# sb-sonata-debug.net
KiCad netlist of a schematic drawn in Altium Designer
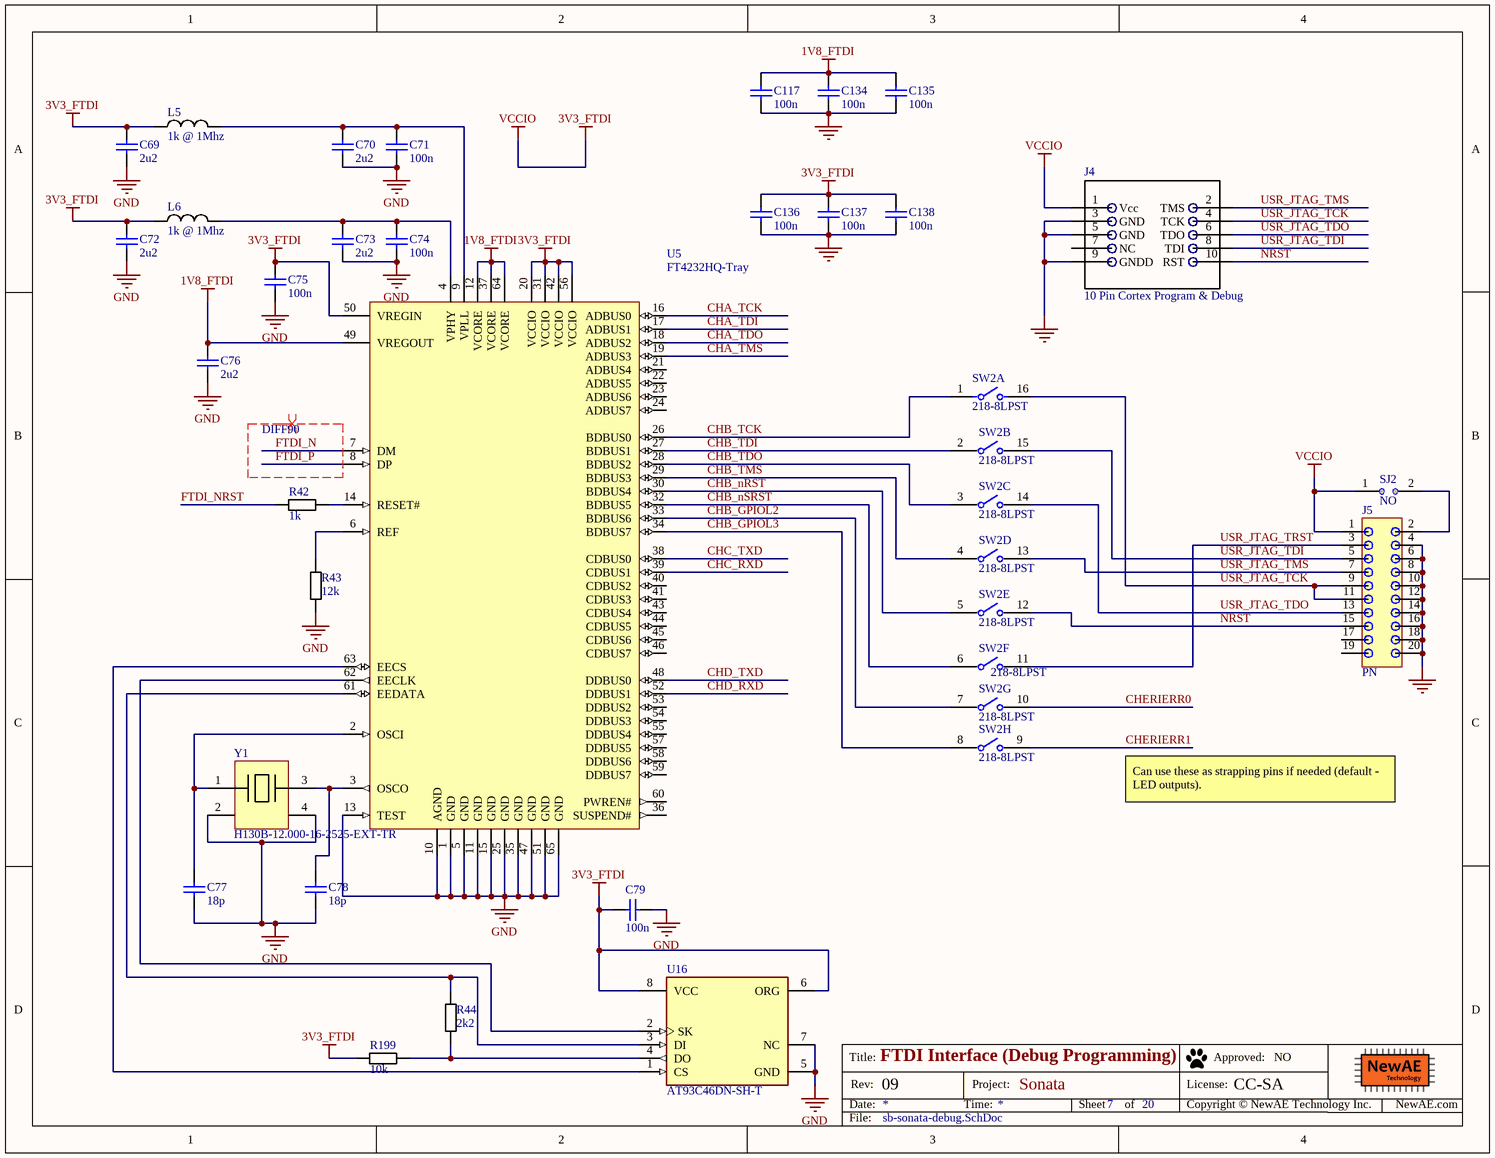
[diagram p0: sb-sonata-debug.SchDoc]

(export (version "E")
  (design (tool "Eeschema 10.0.6"))
  (components
    (comp (ref "C69")
      (value "2u2")
      (footprint "CAPC0603_M")
      (description "2u2, 0603")
      (fields (field (name "PART NUMBER") "CCHIP-2u2-0603"))
      (libsource (lib "NewAE_AltiumLib") (part "CAP"))
    )
    (comp (ref "C70")
      (value "2u2")
      (footprint "CAPC0603_M")
      (description "2u2, 0603")
      (fields (field (name "PART NUMBER") "CCHIP-2u2-0603"))
      (libsource (lib "NewAE_AltiumLib") (part "CAP"))
    )
    (comp (ref "C71")
      (value "100n")
      (footprint "CAPC0402_M")
      (description "100n, 0402")
      (fields (field (name "PART NUMBER") "CCHIP-100n-0402"))
      (libsource (lib "NewAE_AltiumLib") (part "CAP"))
    )
    (comp (ref "C72")
      (value "2u2")
      (footprint "CAPC0603_M")
      (description "2u2, 0603")
      (fields (field (name "PART NUMBER") "CCHIP-2u2-0603"))
      (libsource (lib "NewAE_AltiumLib") (part "CAP"))
    )
    (comp (ref "C73")
      (value "2u2")
      (footprint "CAPC0603_M")
      (description "2u2, 0603")
      (fields (field (name "PART NUMBER") "CCHIP-2u2-0603"))
      (libsource (lib "NewAE_AltiumLib") (part "CAP"))
    )
    (comp (ref "C74")
      (value "100n")
      (footprint "CAPC0402_M")
      (description "100n, 0402")
      (fields (field (name "PART NUMBER") "CCHIP-100n-0402"))
      (libsource (lib "NewAE_AltiumLib") (part "CAP"))
    )
    (comp (ref "C75")
      (value "100n")
      (footprint "CAPC0402_M")
      (description "100n, 0402")
      (fields (field (name "PART NUMBER") "CCHIP-100n-0402"))
      (libsource (lib "NewAE_AltiumLib") (part "CAP"))
    )
    (comp (ref "C76")
      (value "2u2")
      (footprint "CAPC0603_M")
      (description "2u2, 0603")
      (fields (field (name "PART NUMBER") "CCHIP-2u2-0603"))
      (libsource (lib "NewAE_AltiumLib") (part "CAP"))
    )
    (comp (ref "C77")
      (value "18p")
      (footprint "CAPC0402_M")
      (description "18p, 0402")
      (fields (field (name "PART NUMBER") "CCHIP-18p-0402"))
      (libsource (lib "NewAE_AltiumLib") (part "CAP"))
    )
    (comp (ref "C78")
      (value "18p")
      (footprint "CAPC0402_M")
      (description "18p, 0402")
      (fields (field (name "PART NUMBER") "CCHIP-18p-0402"))
      (libsource (lib "NewAE_AltiumLib") (part "CAP"))
    )
    (comp (ref "C79")
      (value "100n")
      (footprint "CAPC0402_M")
      (description "100n, 0402")
      (fields (field (name "PART NUMBER") "CCHIP-100n-0402"))
      (libsource (lib "NewAE_AltiumLib") (part "CAP"))
    )
    (comp (ref "C117")
      (value "100n")
      (footprint "CAPC0402_M")
      (description "100n, 0402")
      (fields (field (name "PART NUMBER") "CCHIP-100n-0402"))
      (libsource (lib "NewAE_AltiumLib") (part "CAP"))
    )
    (comp (ref "C134")
      (value "100n")
      (footprint "CAPC0402_M")
      (description "100n, 0402")
      (fields (field (name "PART NUMBER") "CCHIP-100n-0402"))
      (libsource (lib "NewAE_AltiumLib") (part "CAP"))
    )
    (comp (ref "C135")
      (value "100n")
      (footprint "CAPC0402_M")
      (description "100n, 0402")
      (fields (field (name "PART NUMBER") "CCHIP-100n-0402"))
      (libsource (lib "NewAE_AltiumLib") (part "CAP"))
    )
    (comp (ref "C136")
      (value "100n")
      (footprint "CAPC0402_M")
      (description "100n, 0402")
      (fields (field (name "PART NUMBER") "CCHIP-100n-0402"))
      (libsource (lib "NewAE_AltiumLib") (part "CAP"))
    )
    (comp (ref "C137")
      (value "100n")
      (footprint "CAPC0402_M")
      (description "100n, 0402")
      (fields (field (name "PART NUMBER") "CCHIP-100n-0402"))
      (libsource (lib "NewAE_AltiumLib") (part "CAP"))
    )
    (comp (ref "C138")
      (value "100n")
      (footprint "CAPC0402_M")
      (description "100n, 0402")
      (fields (field (name "PART NUMBER") "CCHIP-100n-0402"))
      (libsource (lib "NewAE_AltiumLib") (part "CAP"))
    )
    (comp (ref "J4")
      (value "10 Pin Cortex Program & Debug")
      (footprint "0.5mm_SMD_Header_5x2")
      (description "10 Pin Cortex Program & Debug 0.5mm pitch")
      (fields (field (name "PART NUMBER") "Cortex_Debug_Header_10Pin"))
      (libsource (lib "NewAE_AltiumLib") (part "Cortex_Debug_Header_10Pin"))
    )
    (comp (ref "J5")
      (value "PN")
      (footprint "CONN_10x2_SHROUDED_2.54mm")
      (description "Header, 2-Row, 20-pin, 0.1\"")
      (fields (field (name "PART NUMBER") "CONN20_2ROW"))
      (libsource (lib "NewAE_AltiumLib") (part "CON20_2ROW"))
    )
    (comp (ref "L5")
      (value "1k @ 1Mhz")
      (footprint "IND_0603")
      (description "Ferrite Beads HI CUR CHIP BD 0603 1000OHMS 25%")
      (fields (field (name "PART NUMBER") "FBCHIP-1k-0603"))
      (libsource (lib "NewAE_AltiumLib") (part "IND"))
    )
    (comp (ref "L6")
      (value "1k @ 1Mhz")
      (footprint "IND_0603")
      (description "Ferrite Beads HI CUR CHIP BD 0603 1000OHMS 25%")
      (fields (field (name "PART NUMBER") "FBCHIP-1k-0603"))
      (libsource (lib "NewAE_AltiumLib") (part "IND"))
    )
    (comp (ref "R42")
      (value "1k")
      (footprint "RESC1005X40N")
      (description "1k res, 0402, 1%, 1/16W")
      (fields (field (name "PART NUMBER") "RCHIP-1K-0402") (field (name "TOLERANCE") "1%"))
      (libsource (lib "NewAE_AltiumLib") (part "RES-EU"))
    )
    (comp (ref "R43")
      (value "12k")
      (footprint "RESC1608X55N")
      (description "12k res, 0603, 1%, 1/10W")
      (fields (field (name "PART NUMBER") "RCHIP-12K-0603") (field (name "TOLERANCE") "1%"))
      (libsource (lib "") (part "RES-EU_2"))
    )
    (comp (ref "R44")
      (value "2k2")
      (footprint "RESC1005X40N")
      (description "2k2 res, 0402, 1%, 1/16W")
      (fields (field (name "PART NUMBER") "RCHIP-2K2-0402") (field (name "TOLERANCE") "1%"))
      (libsource (lib "") (part "RES-EU_2"))
    )
    (comp (ref "R199")
      (value "10k")
      (footprint "RESC1005X40N")
      (description "10k res, 0402, 1%, 1/16W")
      (fields (field (name "PART NUMBER") "RCHIP-10K-0402") (field (name "TOLERANCE") "1%"))
      (libsource (lib "") (part "RES-EU_1"))
    )
    (comp (ref "SJ2")
      (value "NO")
      (footprint "SJ_2S_NO")
      (description "Solder Jumper, NO")
      (fields (field (name "PART NUMBER") "SJ_2S_NO"))
      (libsource (lib "NewAE_AltiumLib") (part "SJ_2S_NO"))
    )
    (comp (ref "SW2")
      (value "218-8LPST")
      (footprint "FP-218-8LPST-MFG")
      (description "SWITCH SLIDE DIP SPST 25MA 24V")
      (libsource (lib "Altium Content Vault") (part "c442af63ff53b934e43635f80d8690e"))
    )
    (comp (ref "U5")
      (value "FT4232HQ-Tray")
      (footprint "QFN64_2_N")
      (description "Quad High Speed USB To Multipurpose UART/MPSSE IC, 64-pin QFN, Tray")
      (fields (field (name "MANUFACTURER") "FTDI"))
      (libsource (lib "Altium Content Vault") (part "COM-UART-FT4232H-QFN64"))
    )
    (comp (ref "U16")
      (value "AT93C46DN-SH-T")
      (footprint "FP-C04-057-SN-MFG")
      (description "IC EEPROM 1K SPI 2MHZ 8SOIC")
      (fields
        (field (name "MANUFACTURER") "Microchip")
        (field (name "OCTOPART") "https://octopart.com/at93c46dn-sh-t-microchip-77759177")
      )
      (libsource (lib "Altium Content Vault") (part "8bb9afc094b350e480db350c7247e52"))
    )
    (comp (ref "Y1")
      (value "H130B-12.000-16-2525-EXT-TR")
      (footprint "5x3.2MM XTAL")
      (description "12MHz ±25ppm Crystal 16pF 35 Ohms 4-SMD, No Lead")
      (fields (field (name "MANUFACTURER PART NUMBER") "H130B-12.000-16-2525-EXT-TR"))
      (libsource (lib "NewAE_AltiumLib") (part "H130B-12.000-16-2525-EXT-TR"))
    )
  )
  (nets
    (net (code "1") (name "/CHA_TCK") (class "Default")
      (node (ref "U5") (pin "16") (pinfunction "ADBUS0_16") (pintype "bidirectional"))
    )
    (net (code "2") (name "/CHA_TDI") (class "Default")
      (node (ref "U5") (pin "17") (pinfunction "ADBUS1_17") (pintype "bidirectional"))
    )
    (net (code "3") (name "/CHA_TDO") (class "Default")
      (node (ref "U5") (pin "18") (pinfunction "ADBUS2_18") (pintype "bidirectional"))
    )
    (net (code "4") (name "/CHA_TMS") (class "Default")
      (node (ref "U5") (pin "19") (pinfunction "ADBUS3_19") (pintype "bidirectional"))
    )
    (net (code "5") (name "/CHB_GPIOL2") (class "Default")
      (node (ref "SW2") (pin "7") (pinfunction "7_7") (pintype "passive"))
      (node (ref "U5") (pin "33") (pinfunction "BDBUS6_33") (pintype "bidirectional"))
    )
    (net (code "6") (name "/CHB_GPIOL3") (class "Default")
      (node (ref "SW2") (pin "8") (pinfunction "8_8") (pintype "passive"))
      (node (ref "U5") (pin "34") (pinfunction "BDBUS7_34") (pintype "bidirectional"))
    )
    (net (code "7") (name "/CHB_TCK") (class "Default")
      (node (ref "SW2") (pin "1") (pinfunction "1_1") (pintype "passive"))
      (node (ref "U5") (pin "26") (pinfunction "BDBUS0_26") (pintype "bidirectional"))
    )
    (net (code "8") (name "/CHB_TDI") (class "Default")
      (node (ref "SW2") (pin "2") (pinfunction "2_2") (pintype "passive"))
      (node (ref "U5") (pin "27") (pinfunction "BDBUS1_27") (pintype "bidirectional"))
    )
    (net (code "9") (name "/CHB_TDO") (class "Default")
      (node (ref "SW2") (pin "3") (pinfunction "3_3") (pintype "passive"))
      (node (ref "U5") (pin "28") (pinfunction "BDBUS2_28") (pintype "bidirectional"))
    )
    (net (code "10") (name "/CHB_TMS") (class "Default")
      (node (ref "SW2") (pin "4") (pinfunction "4_4") (pintype "passive"))
      (node (ref "U5") (pin "29") (pinfunction "BDBUS3_29") (pintype "bidirectional"))
    )
    (net (code "11") (name "/CHB_nRST") (class "Default")
      (node (ref "SW2") (pin "5") (pinfunction "5_5") (pintype "passive"))
      (node (ref "U5") (pin "30") (pinfunction "BDBUS4_30") (pintype "bidirectional"))
    )
    (net (code "12") (name "/CHB_nSRST") (class "Default")
      (node (ref "SW2") (pin "6") (pinfunction "6_6") (pintype "passive"))
      (node (ref "U5") (pin "32") (pinfunction "BDBUS5_32") (pintype "bidirectional"))
    )
    (net (code "13") (name "/CHC_RXD") (class "Default")
      (node (ref "U5") (pin "39") (pinfunction "CDBUS1_39") (pintype "bidirectional"))
    )
    (net (code "14") (name "/CHC_TXD") (class "Default")
      (node (ref "U5") (pin "38") (pinfunction "CDBUS0_38") (pintype "bidirectional"))
    )
    (net (code "15") (name "/CHD_RXD") (class "Default")
      (node (ref "U5") (pin "52") (pinfunction "DDBUS1_52") (pintype "bidirectional"))
    )
    (net (code "16") (name "/CHD_TXD") (class "Default")
      (node (ref "U5") (pin "48") (pinfunction "DDBUS0_48") (pintype "bidirectional"))
    )
    (net (code "17") (name "/CHERIERR0") (class "Default")
      (node (ref "SW2") (pin "10") (pinfunction "10_10") (pintype "passive"))
    )
    (net (code "18") (name "/CHERIERR1") (class "Default")
      (node (ref "SW2") (pin "9") (pinfunction "9_9") (pintype "passive"))
    )
    (net (code "19") (name "/FTDI_N") (class "Default")
      (node (ref "U5") (pin "7") (pinfunction "DM_7") (pintype "input"))
    )
    (net (code "20") (name "/FTDI_NRST") (class "Default")
      (node (ref "R42") (pin "2") (pinfunction "2_2") (pintype "passive"))
    )
    (net (code "21") (name "/FTDI_P") (class "Default")
      (node (ref "U5") (pin "8") (pinfunction "DP_8") (pintype "input"))
    )
    (net (code "22") (name "/NRST") (class "Default")
      (node (ref "J4") (pin "10") (pinfunction "RST_10") (pintype "passive"))
      (node (ref "J5") (pin "15") (pinfunction "9_15") (pintype "passive"))
      (node (ref "SW2") (pin "12") (pinfunction "12_12") (pintype "passive"))
    )
    (net (code "23") (name "/USR_JTAG_TCK") (class "Default")
      (node (ref "J4") (pin "4") (pinfunction "TCK_4") (pintype "passive"))
      (node (ref "J5") (pin "11") (pinfunction "9_11") (pintype "passive"))
      (node (ref "J5") (pin "9") (pinfunction "9_9") (pintype "passive"))
      (node (ref "SW2") (pin "16") (pinfunction "16_16") (pintype "passive"))
    )
    (net (code "24") (name "/USR_JTAG_TDI") (class "Default")
      (node (ref "J4") (pin "8") (pinfunction "TDI_8") (pintype "passive"))
      (node (ref "J5") (pin "5") (pinfunction "5_5") (pintype "passive"))
      (node (ref "SW2") (pin "15") (pinfunction "15_15") (pintype "passive"))
    )
    (net (code "25") (name "/USR_JTAG_TDO") (class "Default")
      (node (ref "J4") (pin "6") (pinfunction "TDO_6") (pintype "passive"))
      (node (ref "J5") (pin "13") (pinfunction "9_13") (pintype "passive"))
      (node (ref "SW2") (pin "14") (pinfunction "14_14") (pintype "passive"))
    )
    (net (code "26") (name "/USR_JTAG_TMS") (class "Default")
      (node (ref "J4") (pin "2") (pinfunction "TMS_2") (pintype "passive"))
      (node (ref "J5") (pin "7") (pinfunction "7_7") (pintype "passive"))
      (node (ref "SW2") (pin "13") (pinfunction "13_13") (pintype "passive"))
    )
    (net (code "27") (name "/USR_JTAG_TRST") (class "Default")
      (node (ref "J5") (pin "3") (pinfunction "3_3") (pintype "passive"))
      (node (ref "SW2") (pin "11") (pinfunction "11_11") (pintype "passive"))
    )
    (net (code "28") (name "1V8_FTDI") (class "Default")
      (node (ref "C117") (pin "1") (pinfunction "1_1") (pintype "passive"))
      (node (ref "C134") (pin "1") (pinfunction "1_1") (pintype "passive"))
      (node (ref "C135") (pin "1") (pinfunction "1_1") (pintype "passive"))
      (node (ref "C76") (pin "1") (pinfunction "1_1") (pintype "passive"))
      (node (ref "U5") (pin "12") (pinfunction "VCORE_12") (pintype "power_in"))
      (node (ref "U5") (pin "37") (pinfunction "VCORE_37") (pintype "power_in"))
      (node (ref "U5") (pin "49") (pinfunction "VREGOUT_49") (pintype "power_in"))
      (node (ref "U5") (pin "64") (pinfunction "VCORE_64") (pintype "power_in"))
    )
    (net (code "29") (name "3V3_FTDI") (class "Default")
      (node (ref "C136") (pin "1") (pinfunction "1_1") (pintype "passive"))
      (node (ref "C137") (pin "1") (pinfunction "1_1") (pintype "passive"))
      (node (ref "C138") (pin "1") (pinfunction "1_1") (pintype "passive"))
      (node (ref "C69") (pin "1") (pinfunction "1_1") (pintype "passive"))
      (node (ref "C72") (pin "1") (pinfunction "1_1") (pintype "passive"))
      (node (ref "C75") (pin "1") (pinfunction "1_1") (pintype "passive"))
      (node (ref "C79") (pin "1") (pinfunction "1_1") (pintype "passive"))
      (node (ref "J4") (pin "1") (pinfunction "Vcc_1") (pintype "passive"))
      (node (ref "J5") (pin "1") (pinfunction "1_1") (pintype "passive"))
      (node (ref "L5") (pin "1") (pinfunction "1_1") (pintype "passive"))
      (node (ref "L6") (pin "1") (pinfunction "1_1") (pintype "passive"))
      (node (ref "R199") (pin "1") (pinfunction "1_1") (pintype "passive"))
      (node (ref "SJ2") (pin "1") (pinfunction "1_1") (pintype "passive"))
      (node (ref "U16") (pin "6") (pinfunction "ORG_6") (pintype "passive"))
      (node (ref "U16") (pin "8") (pinfunction "VCC_8") (pintype "power_in"))
      (node (ref "U5") (pin "20") (pinfunction "VCCIO_20") (pintype "power_in"))
      (node (ref "U5") (pin "31") (pinfunction "VCCIO_31") (pintype "power_in"))
      (node (ref "U5") (pin "42") (pinfunction "VCCIO_42") (pintype "power_in"))
      (node (ref "U5") (pin "50") (pinfunction "VREGIN_50") (pintype "power_in"))
      (node (ref "U5") (pin "56") (pinfunction "VCCIO_56") (pintype "power_in"))
    )
    (net (code "30") (name "GND") (class "Default")
      (node (ref "C117") (pin "2") (pinfunction "2_2") (pintype "passive"))
      (node (ref "C134") (pin "2") (pinfunction "2_2") (pintype "passive"))
      (node (ref "C135") (pin "2") (pinfunction "2_2") (pintype "passive"))
      (node (ref "C136") (pin "2") (pinfunction "2_2") (pintype "passive"))
      (node (ref "C137") (pin "2") (pinfunction "2_2") (pintype "passive"))
      (node (ref "C138") (pin "2") (pinfunction "2_2") (pintype "passive"))
      (node (ref "C69") (pin "2") (pinfunction "2_2") (pintype "passive"))
      (node (ref "C70") (pin "2") (pinfunction "2_2") (pintype "passive"))
      (node (ref "C71") (pin "2") (pinfunction "2_2") (pintype "passive"))
      (node (ref "C72") (pin "2") (pinfunction "2_2") (pintype "passive"))
      (node (ref "C73") (pin "2") (pinfunction "2_2") (pintype "passive"))
      (node (ref "C74") (pin "2") (pinfunction "2_2") (pintype "passive"))
      (node (ref "C75") (pin "2") (pinfunction "2_2") (pintype "passive"))
      (node (ref "C76") (pin "2") (pinfunction "2_2") (pintype "passive"))
      (node (ref "C77") (pin "2") (pinfunction "2_2") (pintype "passive"))
      (node (ref "C78") (pin "2") (pinfunction "2_2") (pintype "passive"))
      (node (ref "C79") (pin "2") (pinfunction "2_2") (pintype "passive"))
      (node (ref "J4") (pin "3") (pinfunction "GND_3") (pintype "passive"))
      (node (ref "J4") (pin "5") (pinfunction "GND_5") (pintype "passive"))
      (node (ref "J4") (pin "9") (pinfunction "GNDD_9") (pintype "passive"))
      (node (ref "J5") (pin "10") (pinfunction "10_10") (pintype "passive"))
      (node (ref "J5") (pin "12") (pinfunction "10_12") (pintype "passive"))
      (node (ref "J5") (pin "14") (pinfunction "10_14") (pintype "passive"))
      (node (ref "J5") (pin "16") (pinfunction "10_16") (pintype "passive"))
      (node (ref "J5") (pin "18") (pinfunction "10_18") (pintype "passive"))
      (node (ref "J5") (pin "20") (pinfunction "10_20") (pintype "passive"))
      (node (ref "J5") (pin "4") (pinfunction "4_4") (pintype "passive"))
      (node (ref "J5") (pin "6") (pinfunction "6_6") (pintype "passive"))
      (node (ref "J5") (pin "8") (pinfunction "8_8") (pintype "passive"))
      (node (ref "R43") (pin "2") (pinfunction "2_2") (pintype "passive"))
      (node (ref "U16") (pin "5") (pinfunction "GND_5") (pintype "power_in"))
      (node (ref "U16") (pin "7") (pinfunction "NC_7") (pintype "passive"))
      (node (ref "U5") (pin "1") (pinfunction "GND_1") (pintype "power_in"))
      (node (ref "U5") (pin "10") (pinfunction "AGND_10") (pintype "power_in"))
      (node (ref "U5") (pin "11") (pinfunction "GND_11") (pintype "power_in"))
      (node (ref "U5") (pin "13") (pinfunction "TEST_13") (pintype "input"))
      (node (ref "U5") (pin "15") (pinfunction "GND_15") (pintype "power_in"))
      (node (ref "U5") (pin "25") (pinfunction "GND_25") (pintype "power_in"))
      (node (ref "U5") (pin "35") (pinfunction "GND_35") (pintype "power_in"))
      (node (ref "U5") (pin "47") (pinfunction "GND_47") (pintype "power_in"))
      (node (ref "U5") (pin "5") (pinfunction "GND_5") (pintype "power_in"))
      (node (ref "U5") (pin "51") (pinfunction "GND_51") (pintype "power_in"))
      (node (ref "U5") (pin "65") (pinfunction "GND_65") (pintype "power_in"))
      (node (ref "Y1") (pin "2") (pinfunction "2_2") (pintype "passive"))
      (node (ref "Y1") (pin "4") (pinfunction "4_4") (pintype "passive"))
    )
    (net (code "31") (name "Net-(J5-Pad2)") (class "Default")
      (node (ref "J5") (pin "2") (pinfunction "2_2") (pintype "passive"))
      (node (ref "SJ2") (pin "2") (pinfunction "2_2") (pintype "passive"))
    )
    (net (code "32") (name "Net-(U5-OSCI)") (class "Default")
      (node (ref "C77") (pin "1") (pinfunction "1_1") (pintype "passive"))
      (node (ref "U5") (pin "2") (pinfunction "OSCI_2") (pintype "input"))
      (node (ref "Y1") (pin "1") (pinfunction "1_1") (pintype "passive"))
    )
    (net (code "33") (name "Net-(U5-OSCO)") (class "Default")
      (node (ref "C78") (pin "1") (pinfunction "1_1") (pintype "passive"))
      (node (ref "U5") (pin "3") (pinfunction "OSCO_3") (pintype "output"))
      (node (ref "Y1") (pin "3") (pinfunction "3_3") (pintype "passive"))
    )
    (net (code "34") (name "Net-(U5-REF)") (class "Default")
      (node (ref "R43") (pin "1") (pinfunction "1_1") (pintype "passive"))
      (node (ref "U5") (pin "6") (pinfunction "REF_6") (pintype "input"))
    )
    (net (code "35") (name "Net-(U5-RESET#)") (class "Default")
      (node (ref "R42") (pin "1") (pinfunction "1_1") (pintype "passive"))
      (node (ref "U5") (pin "14") (pinfunction "RESET#_14") (pintype "input"))
    )
    (net (code "36") (name "Net-(U5-VPHY)") (class "Default")
      (node (ref "C73") (pin "1") (pinfunction "1_1") (pintype "passive"))
      (node (ref "C74") (pin "1") (pinfunction "1_1") (pintype "passive"))
      (node (ref "L6") (pin "2") (pinfunction "2_2") (pintype "passive"))
      (node (ref "U5") (pin "4") (pinfunction "VPHY_4") (pintype "power_in"))
    )
    (net (code "37") (name "Net-(U5-VPLL)") (class "Default")
      (node (ref "C70") (pin "1") (pinfunction "1_1") (pintype "passive"))
      (node (ref "C71") (pin "1") (pinfunction "1_1") (pintype "passive"))
      (node (ref "L5") (pin "2") (pinfunction "2_2") (pintype "passive"))
      (node (ref "U5") (pin "9") (pinfunction "VPLL_9") (pintype "power_in"))
    )
    (net (code "38") (name "Net-(U16-CS)") (class "Default")
      (node (ref "U16") (pin "1") (pinfunction "CS_1") (pintype "input"))
      (node (ref "U5") (pin "63") (pinfunction "EECS_63") (pintype "bidirectional"))
    )
    (net (code "39") (name "Net-(U16-DI)") (class "Default")
      (node (ref "R44") (pin "1") (pinfunction "1_1") (pintype "passive"))
      (node (ref "U16") (pin "3") (pinfunction "DI_3") (pintype "input"))
      (node (ref "U5") (pin "61") (pinfunction "EEDATA_61") (pintype "bidirectional"))
    )
    (net (code "40") (name "Net-(U16-DO)") (class "Default")
      (node (ref "R199") (pin "2") (pinfunction "2_2") (pintype "passive"))
      (node (ref "R44") (pin "2") (pinfunction "2_2") (pintype "passive"))
      (node (ref "U16") (pin "4") (pinfunction "DO_4") (pintype "output"))
    )
    (net (code "41") (name "Net-(U16-SK)") (class "Default")
      (node (ref "U16") (pin "2") (pinfunction "SK_2") (pintype "input"))
      (node (ref "U5") (pin "62") (pinfunction "EECLK_62") (pintype "output"))
    )
    (net (code "42") (name "unconnected-(J4-NC-Pad7)") (class "Default")
      (node (ref "J4") (pin "7") (pinfunction "NC_7") (pintype "passive"))
    )
    (net (code "43") (name "unconnected-(J5-9-Pad17)") (class "Default")
      (node (ref "J5") (pin "17") (pinfunction "9_17") (pintype "passive"))
    )
    (net (code "44") (name "unconnected-(J5-9-Pad19)") (class "Default")
      (node (ref "J5") (pin "19") (pinfunction "9_19") (pintype "passive"))
    )
    (net (code "45") (name "unconnected-(U5-ADBUS4-Pad21)") (class "Default")
      (node (ref "U5") (pin "21") (pinfunction "ADBUS4_21") (pintype "bidirectional"))
    )
    (net (code "46") (name "unconnected-(U5-ADBUS5-Pad22)") (class "Default")
      (node (ref "U5") (pin "22") (pinfunction "ADBUS5_22") (pintype "bidirectional"))
    )
    (net (code "47") (name "unconnected-(U5-ADBUS6-Pad23)") (class "Default")
      (node (ref "U5") (pin "23") (pinfunction "ADBUS6_23") (pintype "bidirectional"))
    )
    (net (code "48") (name "unconnected-(U5-ADBUS7-Pad24)") (class "Default")
      (node (ref "U5") (pin "24") (pinfunction "ADBUS7_24") (pintype "bidirectional"))
    )
    (net (code "49") (name "unconnected-(U5-CDBUS2-Pad40)") (class "Default")
      (node (ref "U5") (pin "40") (pinfunction "CDBUS2_40") (pintype "bidirectional"))
    )
    (net (code "50") (name "unconnected-(U5-CDBUS3-Pad41)") (class "Default")
      (node (ref "U5") (pin "41") (pinfunction "CDBUS3_41") (pintype "bidirectional"))
    )
    (net (code "51") (name "unconnected-(U5-CDBUS4-Pad43)") (class "Default")
      (node (ref "U5") (pin "43") (pinfunction "CDBUS4_43") (pintype "bidirectional"))
    )
    (net (code "52") (name "unconnected-(U5-CDBUS5-Pad44)") (class "Default")
      (node (ref "U5") (pin "44") (pinfunction "CDBUS5_44") (pintype "bidirectional"))
    )
    (net (code "53") (name "unconnected-(U5-CDBUS6-Pad45)") (class "Default")
      (node (ref "U5") (pin "45") (pinfunction "CDBUS6_45") (pintype "bidirectional"))
    )
    (net (code "54") (name "unconnected-(U5-CDBUS7-Pad46)") (class "Default")
      (node (ref "U5") (pin "46") (pinfunction "CDBUS7_46") (pintype "bidirectional"))
    )
    (net (code "55") (name "unconnected-(U5-DDBUS2-Pad53)") (class "Default")
      (node (ref "U5") (pin "53") (pinfunction "DDBUS2_53") (pintype "bidirectional"))
    )
    (net (code "56") (name "unconnected-(U5-DDBUS3-Pad54)") (class "Default")
      (node (ref "U5") (pin "54") (pinfunction "DDBUS3_54") (pintype "bidirectional"))
    )
    (net (code "57") (name "unconnected-(U5-DDBUS4-Pad55)") (class "Default")
      (node (ref "U5") (pin "55") (pinfunction "DDBUS4_55") (pintype "bidirectional"))
    )
    (net (code "58") (name "unconnected-(U5-DDBUS5-Pad57)") (class "Default")
      (node (ref "U5") (pin "57") (pinfunction "DDBUS5_57") (pintype "bidirectional"))
    )
    (net (code "59") (name "unconnected-(U5-DDBUS6-Pad58)") (class "Default")
      (node (ref "U5") (pin "58") (pinfunction "DDBUS6_58") (pintype "bidirectional"))
    )
    (net (code "60") (name "unconnected-(U5-DDBUS7-Pad59)") (class "Default")
      (node (ref "U5") (pin "59") (pinfunction "DDBUS7_59") (pintype "bidirectional"))
    )
    (net (code "61") (name "unconnected-(U5-PWREN#-Pad60)") (class "Default")
      (node (ref "U5") (pin "60") (pinfunction "PWREN#_60") (pintype "output"))
    )
    (net (code "62") (name "unconnected-(U5-SUSPEND#-Pad36)") (class "Default")
      (node (ref "U5") (pin "36") (pinfunction "SUSPEND#_36") (pintype "output"))
    )
  )
)
